# Plasma_Speaker_DIP.net
KiCad netlist of a schematic drawn in Altium Designer
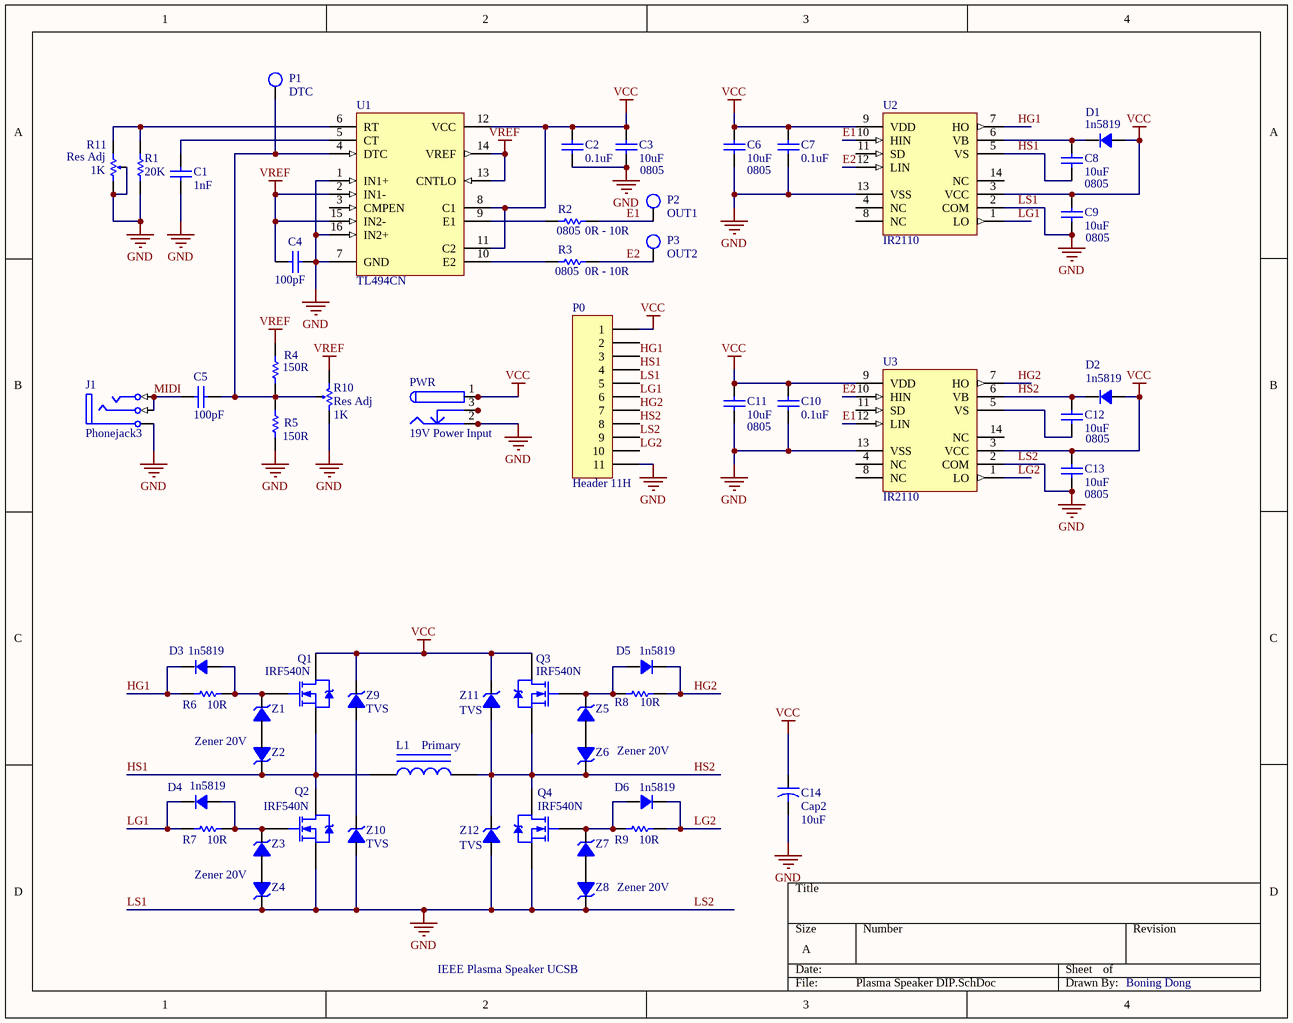
[diagram p0: Plasma Speaker DIP.SchDoc]

(export (version "E")
  (design (tool "Eeschema 10.0.6"))
  (components
    (comp (ref "C1")
      (value "1nF")
      (footprint "RAD-0.3")
      (description "Capacitor")
      (fields (field (name "Comment") "0603") (field (name "PUBLISHER") "Altium Limited"))
      (libsource (lib "Miscellaneous Devices") (part "Cap"))
    )
    (comp (ref "C2")
      (value "0.1uF")
      (footprint "RAD-0.3")
      (description "Capacitor")
      (fields (field (name "Comment") "0603") (field (name "PUBLISHER") "Altium Limited"))
      (libsource (lib "Miscellaneous Devices") (part "Cap"))
    )
    (comp (ref "C3")
      (value "0805")
      (footprint "RAD-0.3")
      (description "Capacitor")
      (fields (field (name "ALTIUM_VALUE") "10uF") (field (name "PUBLISHER") "Altium Limited"))
      (libsource (lib "Miscellaneous Devices") (part "Cap"))
    )
    (comp (ref "C4")
      (value "100pF")
      (footprint "RAD-0.3")
      (description "Capacitor")
      (fields (field (name "Comment") "0603") (field (name "PUBLISHER") "Altium Limited"))
      (libsource (lib "Miscellaneous Devices") (part "Cap"))
    )
    (comp (ref "C5")
      (value "100pF")
      (footprint "RAD-0.3")
      (description "Capacitor")
      (fields (field (name "Comment") "0603") (field (name "PUBLISHER") "Altium Limited"))
      (libsource (lib "Miscellaneous Devices") (part "Cap"))
    )
    (comp (ref "C6")
      (value "0805")
      (footprint "RAD-0.3")
      (description "Capacitor")
      (fields (field (name "ALTIUM_VALUE") "10uF") (field (name "PUBLISHER") "Altium Limited"))
      (libsource (lib "Miscellaneous Devices") (part "Cap"))
    )
    (comp (ref "C7")
      (value "0.1uF")
      (footprint "RAD-0.3")
      (description "Capacitor")
      (fields (field (name "Comment") "0603") (field (name "PUBLISHER") "Altium Limited"))
      (libsource (lib "Miscellaneous Devices") (part "Cap"))
    )
    (comp (ref "C8")
      (value "0805")
      (footprint "RAD-0.3")
      (description "Capacitor")
      (fields (field (name "ALTIUM_VALUE") "10uF") (field (name "PUBLISHER") "Altium Limited"))
      (libsource (lib "Miscellaneous Devices") (part "Cap"))
    )
    (comp (ref "C9")
      (value "0805")
      (footprint "RAD-0.3")
      (description "Capacitor")
      (fields (field (name "ALTIUM_VALUE") "10uF") (field (name "PUBLISHER") "Altium Limited"))
      (libsource (lib "Miscellaneous Devices") (part "Cap"))
    )
    (comp (ref "C10")
      (value "0.1uF")
      (footprint "RAD-0.3")
      (description "Capacitor")
      (fields (field (name "Comment") "0603") (field (name "PUBLISHER") "Altium Limited"))
      (libsource (lib "Miscellaneous Devices") (part "Cap"))
    )
    (comp (ref "C11")
      (value "0805")
      (footprint "RAD-0.3")
      (description "Capacitor")
      (fields (field (name "ALTIUM_VALUE") "10uF") (field (name "PUBLISHER") "Altium Limited"))
      (libsource (lib "Miscellaneous Devices") (part "Cap"))
    )
    (comp (ref "C12")
      (value "0805")
      (footprint "RAD-0.3")
      (description "Capacitor")
      (fields (field (name "ALTIUM_VALUE") "10uF") (field (name "PUBLISHER") "Altium Limited"))
      (libsource (lib "Miscellaneous Devices") (part "Cap"))
    )
    (comp (ref "C13")
      (value "0805")
      (footprint "RAD-0.3")
      (description "Capacitor")
      (fields (field (name "ALTIUM_VALUE") "10uF") (field (name "PUBLISHER") "Altium Limited"))
      (libsource (lib "Miscellaneous Devices") (part "Cap"))
    )
    (comp (ref "C14")
      (value "Cap2")
      (footprint "CAPR5-4X5")
      (description "Capacitor")
      (fields (field (name "ALTIUM_VALUE") "10uF") (field (name "PUBLISHER") "Altium Limited"))
      (libsource (lib "Miscellaneous Devices") (part "Cap2"))
    )
    (comp (ref "D1")
      (value "1n5819")
      (footprint "DIODE-0.7")
      (description "Zener Diode")
      (fields (field (name "PUBLISHER") "Altium Limited"))
      (libsource (lib "Miscellaneous Devices") (part "Diode S"))
    )
    (comp (ref "D2")
      (value "1n5819")
      (footprint "DIODE-0.7")
      (description "Zener Diode")
      (fields (field (name "PUBLISHER") "Altium Limited"))
      (libsource (lib "Miscellaneous Devices") (part "Diode S"))
    )
    (comp (ref "D3")
      (value "1n5819")
      (footprint "DIODE-0.7")
      (description "Zener Diode")
      (fields (field (name "PUBLISHER") "Altium Limited"))
      (libsource (lib "Miscellaneous Devices") (part "Diode S"))
    )
    (comp (ref "D4")
      (value "1n5819")
      (footprint "DIODE-0.7")
      (description "Zener Diode")
      (fields (field (name "PUBLISHER") "Altium Limited"))
      (libsource (lib "Miscellaneous Devices") (part "Diode S"))
    )
    (comp (ref "D5")
      (value "1n5819")
      (footprint "DIODE-0.7")
      (description "Zener Diode")
      (fields (field (name "PUBLISHER") "Altium Limited"))
      (libsource (lib "Miscellaneous Devices") (part "Diode S"))
    )
    (comp (ref "D6")
      (value "1n5819")
      (footprint "DIODE-0.7")
      (description "Zener Diode")
      (fields (field (name "PUBLISHER") "Altium Limited"))
      (libsource (lib "Miscellaneous Devices") (part "Diode S"))
    )
    (comp (ref "J1")
      (value "Phonejack3")
      (footprint "JACK/6-V3")
      (description "Jack Socket, 1/4\" [6.5mm], Thru-Hole, Vertical, 3-Conductor Open Circuit (Non-Normalling)")
      (fields (field (name "PUBLISHER") "Altium Limited"))
      (libsource (lib "Miscellaneous Connectors") (part "Phonejack3"))
    )
    (comp (ref "L1")
      (value "Primary")
      (footprint "AXIAL-0.9")
      (description "Magnetic-Core Inductor")
      (fields (field (name "Comment") "Inductor Iron") (field (name "PUBLISHER") "Altium Limited"))
      (libsource (lib "Miscellaneous Devices") (part "Inductor Iron"))
    )
    (comp (ref "P0")
      (value "Header 11H")
      (footprint "HDR1X11H")
      (description "Header, 11-Pin, Right Angle")
      (fields (field (name "PUBLISHER") "Altium Limited"))
      (libsource (lib "Miscellaneous Connectors") (part "Header 11H"))
    )
    (comp (ref "P1")
      (value "DTC")
      (description "Test Point")
      (libsource (lib "Miscellaneous Connectors") (part "TP"))
    )
    (comp (ref "P2")
      (value "OUT1")
      (description "Test Point")
      (libsource (lib "Miscellaneous Connectors") (part "TP"))
    )
    (comp (ref "P3")
      (value "OUT2")
      (description "Test Point")
      (libsource (lib "Miscellaneous Connectors") (part "TP"))
    )
    (comp (ref "PWR")
      (value "19V Power Input")
      (footprint "KLD-0202")
      (description "Low Voltage Power Supply Connector")
      (fields (field (name "PUBLISHER") "Altium Limited"))
      (libsource (lib "Miscellaneous Connectors") (part "PWR2.5"))
    )
    (comp (ref "Q1")
      (value "IRF540N")
      (footprint "TO-220AB")
      (description "N-Channel Power MOSFET")
      (fields (field (name "PUBLISHER") "Altium Limited"))
      (libsource (lib "Transistor") (part "IRF540N"))
    )
    (comp (ref "Q2")
      (value "IRF540N")
      (footprint "TO-220AB")
      (description "N-Channel Power MOSFET")
      (fields (field (name "PUBLISHER") "Altium Limited"))
      (libsource (lib "Transistor") (part "IRF540N"))
    )
    (comp (ref "Q3")
      (value "IRF540N")
      (footprint "TO-220AB")
      (description "N-Channel Power MOSFET")
      (fields (field (name "PUBLISHER") "Altium Limited"))
      (libsource (lib "Transistor") (part "IRF540N"))
    )
    (comp (ref "Q4")
      (value "IRF540N")
      (footprint "TO-220AB")
      (description "N-Channel Power MOSFET")
      (fields (field (name "PUBLISHER") "Altium Limited"))
      (libsource (lib "Transistor") (part "IRF540N"))
    )
    (comp (ref "R1")
      (value "20K")
      (footprint "AXIAL-0.3")
      (description "Resistor")
      (fields (field (name "Comment") "0603") (field (name "PUBLISHER") "Altium Limited"))
      (libsource (lib "Miscellaneous Devices") (part "Res1"))
    )
    (comp (ref "R2")
      (value "0805")
      (footprint "AXIAL-0.3")
      (description "Resistor")
      (fields (field (name "ALTIUM_VALUE") "0R - 10R") (field (name "PUBLISHER") "Altium Limited"))
      (libsource (lib "Miscellaneous Devices") (part "Res1"))
    )
    (comp (ref "R3")
      (value "0805")
      (footprint "AXIAL-0.3")
      (description "Resistor")
      (fields (field (name "ALTIUM_VALUE") "0R - 10R") (field (name "PUBLISHER") "Altium Limited"))
      (libsource (lib "Miscellaneous Devices") (part "Res1"))
    )
    (comp (ref "R4")
      (value "150R")
      (footprint "AXIAL-0.3")
      (description "Resistor")
      (fields (field (name "Comment") "0603") (field (name "PUBLISHER") "Altium Limited"))
      (libsource (lib "Miscellaneous Devices") (part "Res1"))
    )
    (comp (ref "R5")
      (value "150R")
      (footprint "AXIAL-0.3")
      (description "Resistor")
      (fields (field (name "Comment") "0603") (field (name "PUBLISHER") "Altium Limited"))
      (libsource (lib "Miscellaneous Devices") (part "Res1"))
    )
    (comp (ref "R6")
      (value "10R")
      (footprint "AXIAL-0.3")
      (description "Resistor")
      (fields (field (name "Comment") "0805") (field (name "PUBLISHER") "Altium Limited"))
      (libsource (lib "Miscellaneous Devices") (part "Res1"))
    )
    (comp (ref "R7")
      (value "10R")
      (footprint "AXIAL-0.3")
      (description "Resistor")
      (fields (field (name "Comment") "0805") (field (name "PUBLISHER") "Altium Limited"))
      (libsource (lib "Miscellaneous Devices") (part "Res1"))
    )
    (comp (ref "R8")
      (value "10R")
      (footprint "AXIAL-0.3")
      (description "Resistor")
      (fields (field (name "Comment") "0805") (field (name "PUBLISHER") "Altium Limited"))
      (libsource (lib "Miscellaneous Devices") (part "Res1"))
    )
    (comp (ref "R9")
      (value "10R")
      (footprint "AXIAL-0.3")
      (description "Resistor")
      (fields (field (name "Comment") "0805") (field (name "PUBLISHER") "Altium Limited"))
      (libsource (lib "Miscellaneous Devices") (part "Res1"))
    )
    (comp (ref "R10")
      (value "Res Adj")
      (footprint "AXIAL-0.3")
      (description "Resistor")
      (fields (field (name "ALTIUM_VALUE") "1K") (field (name "PUBLISHER") "Altium Limited"))
      (libsource (lib "Miscellaneous Devices") (part "Res Adj"))
    )
    (comp (ref "R11")
      (value "Res Adj")
      (footprint "AXIAL-0.3")
      (description "Resistor")
      (fields (field (name "ALTIUM_VALUE") "1K") (field (name "PUBLISHER") "Altium Limited"))
      (libsource (lib "Miscellaneous Devices") (part "Res Adj"))
    )
    (comp (ref "U1")
      (value "TL494CN")
      (footprint "648-06")
      (description "Switchmode Pulse Width Modulation Control Circuit")
      (fields (field (name "PUBLISHER") "Altium Limited"))
      (libsource (lib "Motorola Power Mgt SMPS Controller") (part "TL494CN"))
    )
    (comp (ref "U2")
      (value "IR2110")
      (footprint "PDIP14")
      (description "High and Low Side Driver")
      (fields (field (name "PUBLISHER") "Altium Limited"))
      (libsource (lib "IR Interface Bridge Driver") (part "IR2110"))
    )
    (comp (ref "U3")
      (value "IR2110")
      (footprint "PDIP14")
      (description "High and Low Side Driver")
      (fields (field (name "PUBLISHER") "Altium Limited"))
      (libsource (lib "IR Interface Bridge Driver") (part "IR2110"))
    )
    (comp (ref "Z1")
      (value "Zener 20V")
      (footprint "DIODE-0.7")
      (description "Zener Diode")
      (fields (field (name "PUBLISHER") "Altium Limited"))
      (libsource (lib "Miscellaneous Devices") (part "Zener"))
    )
    (comp (ref "Z2")
      (value "Zener")
      (footprint "DIODE-0.7")
      (description "Zener Diode")
      (fields (field (name "PUBLISHER") "Altium Limited"))
      (libsource (lib "Miscellaneous Devices") (part "Zener"))
    )
    (comp (ref "Z3")
      (value "Zener 20V")
      (footprint "DIODE-0.7")
      (description "Zener Diode")
      (fields (field (name "PUBLISHER") "Altium Limited"))
      (libsource (lib "Miscellaneous Devices") (part "Zener"))
    )
    (comp (ref "Z4")
      (value "Zener")
      (footprint "DIODE-0.7")
      (description "Zener Diode")
      (fields (field (name "PUBLISHER") "Altium Limited"))
      (libsource (lib "Miscellaneous Devices") (part "Zener"))
    )
    (comp (ref "Z5")
      (value "Zener 20V")
      (footprint "DIODE-0.7")
      (description "Zener Diode")
      (fields (field (name "PUBLISHER") "Altium Limited"))
      (libsource (lib "Miscellaneous Devices") (part "Zener"))
    )
    (comp (ref "Z6")
      (value "Zener")
      (footprint "DIODE-0.7")
      (description "Zener Diode")
      (fields (field (name "PUBLISHER") "Altium Limited"))
      (libsource (lib "Miscellaneous Devices") (part "Zener"))
    )
    (comp (ref "Z7")
      (value "Zener 20V")
      (footprint "DIODE-0.7")
      (description "Zener Diode")
      (fields (field (name "PUBLISHER") "Altium Limited"))
      (libsource (lib "Miscellaneous Devices") (part "Zener"))
    )
    (comp (ref "Z8")
      (value "Zener")
      (footprint "DIODE-0.7")
      (description "Zener Diode")
      (fields (field (name "PUBLISHER") "Altium Limited"))
      (libsource (lib "Miscellaneous Devices") (part "Zener"))
    )
    (comp (ref "Z9")
      (value "TVS")
      (footprint "DIODE-0.7")
      (description "Zener Diode")
      (fields (field (name "PUBLISHER") "Altium Limited"))
      (libsource (lib "Miscellaneous Devices") (part "Zener"))
    )
    (comp (ref "Z10")
      (value "TVS")
      (footprint "DIODE-0.7")
      (description "Zener Diode")
      (fields (field (name "PUBLISHER") "Altium Limited"))
      (libsource (lib "Miscellaneous Devices") (part "Zener"))
    )
    (comp (ref "Z11")
      (value "TVS")
      (footprint "DIODE-0.7")
      (description "Zener Diode")
      (fields (field (name "PUBLISHER") "Altium Limited"))
      (libsource (lib "Miscellaneous Devices") (part "Zener"))
    )
    (comp (ref "Z12")
      (value "TVS")
      (footprint "DIODE-0.7")
      (description "Zener Diode")
      (fields (field (name "PUBLISHER") "Altium Limited"))
      (libsource (lib "Miscellaneous Devices") (part "Zener"))
    )
  )
  (nets
    (net (code "1") (name "/E1") (class "Default")
      (node (ref "P2") (pin "1") (pinfunction "1_1") (pintype "passive"))
      (node (ref "R2") (pin "1") (pinfunction "1_1") (pintype "passive"))
      (node (ref "U2") (pin "10") (pinfunction "HIN_10") (pintype "input"))
      (node (ref "U3") (pin "12") (pinfunction "LIN_12") (pintype "input"))
    )
    (net (code "2") (name "/E2") (class "Default")
      (node (ref "P3") (pin "1") (pinfunction "1_1") (pintype "passive"))
      (node (ref "R3") (pin "1") (pinfunction "1_1") (pintype "passive"))
      (node (ref "U2") (pin "12") (pinfunction "LIN_12") (pintype "input"))
      (node (ref "U3") (pin "10") (pinfunction "HIN_10") (pintype "input"))
    )
    (net (code "3") (name "/HG1") (class "Default")
      (node (ref "D3") (pin "2") (pinfunction "2_2") (pintype "passive"))
      (node (ref "P0") (pin "3") (pinfunction "3_3") (pintype "passive"))
      (node (ref "R6") (pin "2") (pinfunction "2_2") (pintype "passive"))
      (node (ref "U2") (pin "7") (pinfunction "HO_7") (pintype "output"))
    )
    (net (code "4") (name "/HG2") (class "Default")
      (node (ref "D5") (pin "2") (pinfunction "2_2") (pintype "passive"))
      (node (ref "P0") (pin "7") (pinfunction "7_7") (pintype "passive"))
      (node (ref "R8") (pin "1") (pinfunction "1_1") (pintype "passive"))
      (node (ref "U3") (pin "7") (pinfunction "HO_7") (pintype "output"))
    )
    (net (code "5") (name "/HS1") (class "Default")
      (node (ref "C8") (pin "1") (pinfunction "1_1") (pintype "passive"))
      (node (ref "L1") (pin "1") (pinfunction "1_1") (pintype "passive"))
      (node (ref "P0") (pin "4") (pinfunction "4_4") (pintype "passive"))
      (node (ref "Q1") (pin "3") (pinfunction "S_3") (pintype "passive"))
      (node (ref "Q2") (pin "2") (pinfunction "D_2") (pintype "passive"))
      (node (ref "U2") (pin "5") (pinfunction "VS_5") (pintype "power_in"))
      (node (ref "Z2") (pin "2") (pinfunction "2_2") (pintype "passive"))
    )
    (net (code "6") (name "/HS2") (class "Default")
      (node (ref "C12") (pin "2") (pinfunction "2_2") (pintype "passive"))
      (node (ref "D2") (pin "2") (pinfunction "2_2") (pintype "passive"))
      (node (ref "L1") (pin "2") (pinfunction "2_2") (pintype "passive"))
      (node (ref "P0") (pin "8") (pinfunction "8_8") (pintype "passive"))
      (node (ref "Q3") (pin "3") (pinfunction "S_3") (pintype "passive"))
      (node (ref "Q4") (pin "2") (pinfunction "D_2") (pintype "passive"))
      (node (ref "U3") (pin "6") (pinfunction "VB_6") (pintype "power_in"))
      (node (ref "Z11") (pin "1") (pinfunction "1_1") (pintype "passive"))
      (node (ref "Z12") (pin "2") (pinfunction "2_2") (pintype "passive"))
      (node (ref "Z6") (pin "2") (pinfunction "2_2") (pintype "passive"))
    )
    (net (code "7") (name "/LG1") (class "Default")
      (node (ref "D4") (pin "2") (pinfunction "2_2") (pintype "passive"))
      (node (ref "P0") (pin "6") (pinfunction "6_6") (pintype "passive"))
      (node (ref "R7") (pin "2") (pinfunction "2_2") (pintype "passive"))
      (node (ref "U2") (pin "1") (pinfunction "LO_1") (pintype "output"))
    )
    (net (code "8") (name "/LG2") (class "Default")
      (node (ref "D6") (pin "2") (pinfunction "2_2") (pintype "passive"))
      (node (ref "P0") (pin "10") (pinfunction "10_10") (pintype "passive"))
      (node (ref "R9") (pin "1") (pinfunction "1_1") (pintype "passive"))
      (node (ref "U3") (pin "1") (pinfunction "LO_1") (pintype "output"))
    )
    (net (code "9") (name "/MIDI") (class "Default")
      (node (ref "C5") (pin "1") (pinfunction "1_1") (pintype "passive"))
      (node (ref "J1") (pin "1") (pinfunction "T_1") (pintype "input"))
      (node (ref "J1") (pin "3") (pinfunction "R_3") (pintype "input"))
    )
    (net (code "10") (name "GND") (class "Default")
      (node (ref "C1") (pin "1") (pinfunction "1_1") (pintype "passive"))
      (node (ref "C10") (pin "1") (pinfunction "1_1") (pintype "passive"))
      (node (ref "C11") (pin "1") (pinfunction "1_1") (pintype "passive"))
      (node (ref "C13") (pin "1") (pinfunction "1_1") (pintype "passive"))
      (node (ref "C14") (pin "2") (pinfunction "2_2") (pintype "passive"))
      (node (ref "C2") (pin "1") (pinfunction "1_1") (pintype "passive"))
      (node (ref "C3") (pin "1") (pinfunction "1_1") (pintype "passive"))
      (node (ref "C4") (pin "1") (pinfunction "1_1") (pintype "passive"))
      (node (ref "C6") (pin "1") (pinfunction "1_1") (pintype "passive"))
      (node (ref "C7") (pin "1") (pinfunction "1_1") (pintype "passive"))
      (node (ref "C9") (pin "1") (pinfunction "1_1") (pintype "passive"))
      (node (ref "J1") (pin "5") (pinfunction "S_5") (pintype "power_in"))
      (node (ref "P0") (pin "11") (pinfunction "11_11") (pintype "passive"))
      (node (ref "P0") (pin "5") (pinfunction "5_5") (pintype "passive"))
      (node (ref "P0") (pin "9") (pinfunction "9_9") (pintype "passive"))
      (node (ref "PWR") (pin "2") (pinfunction "2_2") (pintype "power_in"))
      (node (ref "PWR") (pin "2A") (pinfunction "2A_2A") (pintype "power_in"))
      (node (ref "PWR") (pin "2B") (pinfunction "2B_2B") (pintype "power_in"))
      (node (ref "Q2") (pin "3") (pinfunction "S_3") (pintype "passive"))
      (node (ref "Q4") (pin "3") (pinfunction "S_3") (pintype "passive"))
      (node (ref "R1") (pin "1") (pinfunction "1_1") (pintype "passive"))
      (node (ref "R10") (pin "3") (pinfunction "3_3") (pintype "passive"))
      (node (ref "R11") (pin "2") (pinfunction "2_2") (pintype "passive"))
      (node (ref "R11") (pin "3") (pinfunction "3_3") (pintype "passive"))
      (node (ref "R5") (pin "1") (pinfunction "1_1") (pintype "passive"))
      (node (ref "U1") (pin "1") (pinfunction "IN1+_1") (pintype "input"))
      (node (ref "U1") (pin "16") (pinfunction "IN2+_16") (pintype "input"))
      (node (ref "U1") (pin "7") (pinfunction "GND_7") (pintype "power_in"))
      (node (ref "U2") (pin "13") (pinfunction "VSS_13") (pintype "power_in"))
      (node (ref "U2") (pin "2") (pinfunction "COM_2") (pintype "power_in"))
      (node (ref "U3") (pin "13") (pinfunction "VSS_13") (pintype "power_in"))
      (node (ref "U3") (pin "2") (pinfunction "COM_2") (pintype "power_in"))
      (node (ref "Z10") (pin "1") (pinfunction "1_1") (pintype "passive"))
      (node (ref "Z12") (pin "1") (pinfunction "1_1") (pintype "passive"))
      (node (ref "Z4") (pin "2") (pinfunction "2_2") (pintype "passive"))
      (node (ref "Z8") (pin "2") (pinfunction "2_2") (pintype "passive"))
    )
    (net (code "11") (name "Net-(PWR-Pad3)") (class "Default")
      (node (ref "PWR") (pin "3") (pinfunction "3_3") (pintype "power_in"))
      (node (ref "PWR") (pin "3A") (pinfunction "3A_3A") (pintype "power_in"))
      (node (ref "PWR") (pin "3B") (pinfunction "3B_3B") (pintype "power_in"))
    )
    (net (code "12") (name "Net-(Q1-G)") (class "Default")
      (node (ref "D3") (pin "1") (pinfunction "1_1") (pintype "passive"))
      (node (ref "Q1") (pin "1") (pinfunction "G_1") (pintype "passive"))
      (node (ref "R6") (pin "1") (pinfunction "1_1") (pintype "passive"))
      (node (ref "Z1") (pin "2") (pinfunction "2_2") (pintype "passive"))
    )
    (net (code "13") (name "Net-(Q2-G)") (class "Default")
      (node (ref "D4") (pin "1") (pinfunction "1_1") (pintype "passive"))
      (node (ref "Q2") (pin "1") (pinfunction "G_1") (pintype "passive"))
      (node (ref "R7") (pin "1") (pinfunction "1_1") (pintype "passive"))
      (node (ref "Z3") (pin "2") (pinfunction "2_2") (pintype "passive"))
    )
    (net (code "14") (name "Net-(Q3-G)") (class "Default")
      (node (ref "D5") (pin "1") (pinfunction "1_1") (pintype "passive"))
      (node (ref "Q3") (pin "1") (pinfunction "G_1") (pintype "passive"))
      (node (ref "R8") (pin "2") (pinfunction "2_2") (pintype "passive"))
      (node (ref "Z5") (pin "2") (pinfunction "2_2") (pintype "passive"))
    )
    (net (code "15") (name "Net-(Q4-G)") (class "Default")
      (node (ref "D6") (pin "1") (pinfunction "1_1") (pintype "passive"))
      (node (ref "Q4") (pin "1") (pinfunction "G_1") (pintype "passive"))
      (node (ref "R9") (pin "2") (pinfunction "2_2") (pintype "passive"))
      (node (ref "Z7") (pin "2") (pinfunction "2_2") (pintype "passive"))
    )
    (net (code "16") (name "Net-(U1-CT)") (class "Default")
      (node (ref "C1") (pin "2") (pinfunction "2_2") (pintype "passive"))
      (node (ref "U1") (pin "5") (pinfunction "CT_5") (pintype "passive"))
    )
    (net (code "17") (name "Net-(U1-DTC)") (class "Default")
      (node (ref "C5") (pin "2") (pinfunction "2_2") (pintype "passive"))
      (node (ref "P1") (pin "1") (pinfunction "1_1") (pintype "passive"))
      (node (ref "R10") (pin "2") (pinfunction "2_2") (pintype "passive"))
      (node (ref "R4") (pin "1") (pinfunction "1_1") (pintype "passive"))
      (node (ref "R5") (pin "2") (pinfunction "2_2") (pintype "passive"))
      (node (ref "U1") (pin "4") (pinfunction "DTC_4") (pintype "input"))
    )
    (net (code "18") (name "Net-(U1-E1)") (class "Default")
      (node (ref "R2") (pin "2") (pinfunction "2_2") (pintype "passive"))
      (node (ref "U1") (pin "9") (pinfunction "E1_9") (pintype "passive"))
    )
    (net (code "19") (name "Net-(U1-E2)") (class "Default")
      (node (ref "R3") (pin "2") (pinfunction "2_2") (pintype "passive"))
      (node (ref "U1") (pin "10") (pinfunction "E2_10") (pintype "passive"))
    )
    (net (code "20") (name "Net-(U1-RT)") (class "Default")
      (node (ref "R1") (pin "2") (pinfunction "2_2") (pintype "passive"))
      (node (ref "R11") (pin "1") (pinfunction "1_1") (pintype "passive"))
      (node (ref "U1") (pin "6") (pinfunction "RT_6") (pintype "passive"))
    )
    (net (code "21") (name "Net-(U2-VB)") (class "Default")
      (node (ref "C8") (pin "2") (pinfunction "2_2") (pintype "passive"))
      (node (ref "D1") (pin "2") (pinfunction "2_2") (pintype "passive"))
      (node (ref "U2") (pin "6") (pinfunction "VB_6") (pintype "power_in"))
    )
    (net (code "22") (name "Net-(U3-VS)") (class "Default")
      (node (ref "C12") (pin "1") (pinfunction "1_1") (pintype "passive"))
      (node (ref "U3") (pin "5") (pinfunction "VS_5") (pintype "power_in"))
    )
    (net (code "23") (name "Net-(Z1-Pad1)") (class "Default")
      (node (ref "Z1") (pin "1") (pinfunction "1_1") (pintype "passive"))
      (node (ref "Z2") (pin "1") (pinfunction "1_1") (pintype "passive"))
    )
    (net (code "24") (name "Net-(Z3-Pad1)") (class "Default")
      (node (ref "Z3") (pin "1") (pinfunction "1_1") (pintype "passive"))
      (node (ref "Z4") (pin "1") (pinfunction "1_1") (pintype "passive"))
    )
    (net (code "25") (name "Net-(Z5-Pad1)") (class "Default")
      (node (ref "Z5") (pin "1") (pinfunction "1_1") (pintype "passive"))
      (node (ref "Z6") (pin "1") (pinfunction "1_1") (pintype "passive"))
    )
    (net (code "26") (name "Net-(Z7-Pad1)") (class "Default")
      (node (ref "Z7") (pin "1") (pinfunction "1_1") (pintype "passive"))
      (node (ref "Z8") (pin "1") (pinfunction "1_1") (pintype "passive"))
    )
    (net (code "27") (name "Net-(Z10-Pad2)") (class "Default")
      (node (ref "Z10") (pin "2") (pinfunction "2_2") (pintype "passive"))
      (node (ref "Z9") (pin "1") (pinfunction "1_1") (pintype "passive"))
    )
    (net (code "28") (name "VCC") (class "Default")
      (node (ref "C10") (pin "2") (pinfunction "2_2") (pintype "passive"))
      (node (ref "C11") (pin "2") (pinfunction "2_2") (pintype "passive"))
      (node (ref "C13") (pin "2") (pinfunction "2_2") (pintype "passive"))
      (node (ref "C14") (pin "1") (pinfunction "1_1") (pintype "passive"))
      (node (ref "C2") (pin "2") (pinfunction "2_2") (pintype "passive"))
      (node (ref "C3") (pin "2") (pinfunction "2_2") (pintype "passive"))
      (node (ref "C6") (pin "2") (pinfunction "2_2") (pintype "passive"))
      (node (ref "C7") (pin "2") (pinfunction "2_2") (pintype "passive"))
      (node (ref "C9") (pin "2") (pinfunction "2_2") (pintype "passive"))
      (node (ref "D1") (pin "1") (pinfunction "1_1") (pintype "passive"))
      (node (ref "D2") (pin "1") (pinfunction "1_1") (pintype "passive"))
      (node (ref "P0") (pin "1") (pinfunction "1_1") (pintype "passive"))
      (node (ref "PWR") (pin "1") (pinfunction "1_1") (pintype "power_in"))
      (node (ref "PWR") (pin "1A") (pinfunction "1A_1A") (pintype "power_in"))
      (node (ref "PWR") (pin "1B") (pinfunction "1B_1B") (pintype "power_in"))
      (node (ref "Q1") (pin "2") (pinfunction "D_2") (pintype "passive"))
      (node (ref "Q3") (pin "2") (pinfunction "D_2") (pintype "passive"))
      (node (ref "U1") (pin "11") (pinfunction "C2_11") (pintype "passive"))
      (node (ref "U1") (pin "12") (pinfunction "VCC_12") (pintype "power_in"))
      (node (ref "U1") (pin "8") (pinfunction "C1_8") (pintype "passive"))
      (node (ref "U2") (pin "3") (pinfunction "VCC_3") (pintype "power_in"))
      (node (ref "U2") (pin "9") (pinfunction "VDD_9") (pintype "power_in"))
      (node (ref "U3") (pin "3") (pinfunction "VCC_3") (pintype "power_in"))
      (node (ref "U3") (pin "9") (pinfunction "VDD_9") (pintype "power_in"))
      (node (ref "Z11") (pin "2") (pinfunction "2_2") (pintype "passive"))
      (node (ref "Z9") (pin "2") (pinfunction "2_2") (pintype "passive"))
    )
    (net (code "29") (name "VREF") (class "Default")
      (node (ref "C4") (pin "2") (pinfunction "2_2") (pintype "passive"))
      (node (ref "R10") (pin "1") (pinfunction "1_1") (pintype "passive"))
      (node (ref "R4") (pin "2") (pinfunction "2_2") (pintype "passive"))
      (node (ref "U1") (pin "13") (pinfunction "CNTLO_13") (pintype "input"))
      (node (ref "U1") (pin "14") (pinfunction "VREF_14") (pintype "output"))
      (node (ref "U1") (pin "15") (pinfunction "IN2-_15") (pintype "input"))
      (node (ref "U1") (pin "2") (pinfunction "IN1-_2") (pintype "input"))
    )
    (net (code "30") (name "unconnected-(P0-Pad2)") (class "Default")
      (node (ref "P0") (pin "2") (pinfunction "2_2") (pintype "passive"))
    )
    (net (code "31") (name "unconnected-(U1-CMPEN-Pad3)") (class "Default")
      (node (ref "U1") (pin "3") (pinfunction "CMPEN_3") (pintype "input"))
    )
    (net (code "32") (name "unconnected-(U2-NC-Pad4)") (class "Default")
      (node (ref "U2") (pin "4") (pinfunction "NC_4") (pintype "passive"))
    )
    (net (code "33") (name "unconnected-(U2-NC-Pad8)") (class "Default")
      (node (ref "U2") (pin "8") (pinfunction "NC_8") (pintype "passive"))
    )
    (net (code "34") (name "unconnected-(U2-NC-Pad14)") (class "Default")
      (node (ref "U2") (pin "14") (pinfunction "NC_14") (pintype "passive"))
    )
    (net (code "35") (name "unconnected-(U2-SD-Pad11)") (class "Default")
      (node (ref "U2") (pin "11") (pinfunction "SD_11") (pintype "input"))
    )
    (net (code "36") (name "unconnected-(U3-NC-Pad4)") (class "Default")
      (node (ref "U3") (pin "4") (pinfunction "NC_4") (pintype "passive"))
    )
    (net (code "37") (name "unconnected-(U3-NC-Pad8)") (class "Default")
      (node (ref "U3") (pin "8") (pinfunction "NC_8") (pintype "passive"))
    )
    (net (code "38") (name "unconnected-(U3-NC-Pad14)") (class "Default")
      (node (ref "U3") (pin "14") (pinfunction "NC_14") (pintype "passive"))
    )
    (net (code "39") (name "unconnected-(U3-SD-Pad11)") (class "Default")
      (node (ref "U3") (pin "11") (pinfunction "SD_11") (pintype "input"))
    )
  )
)
